# MCU.net
KiCad netlist of a schematic drawn in Altium Designer
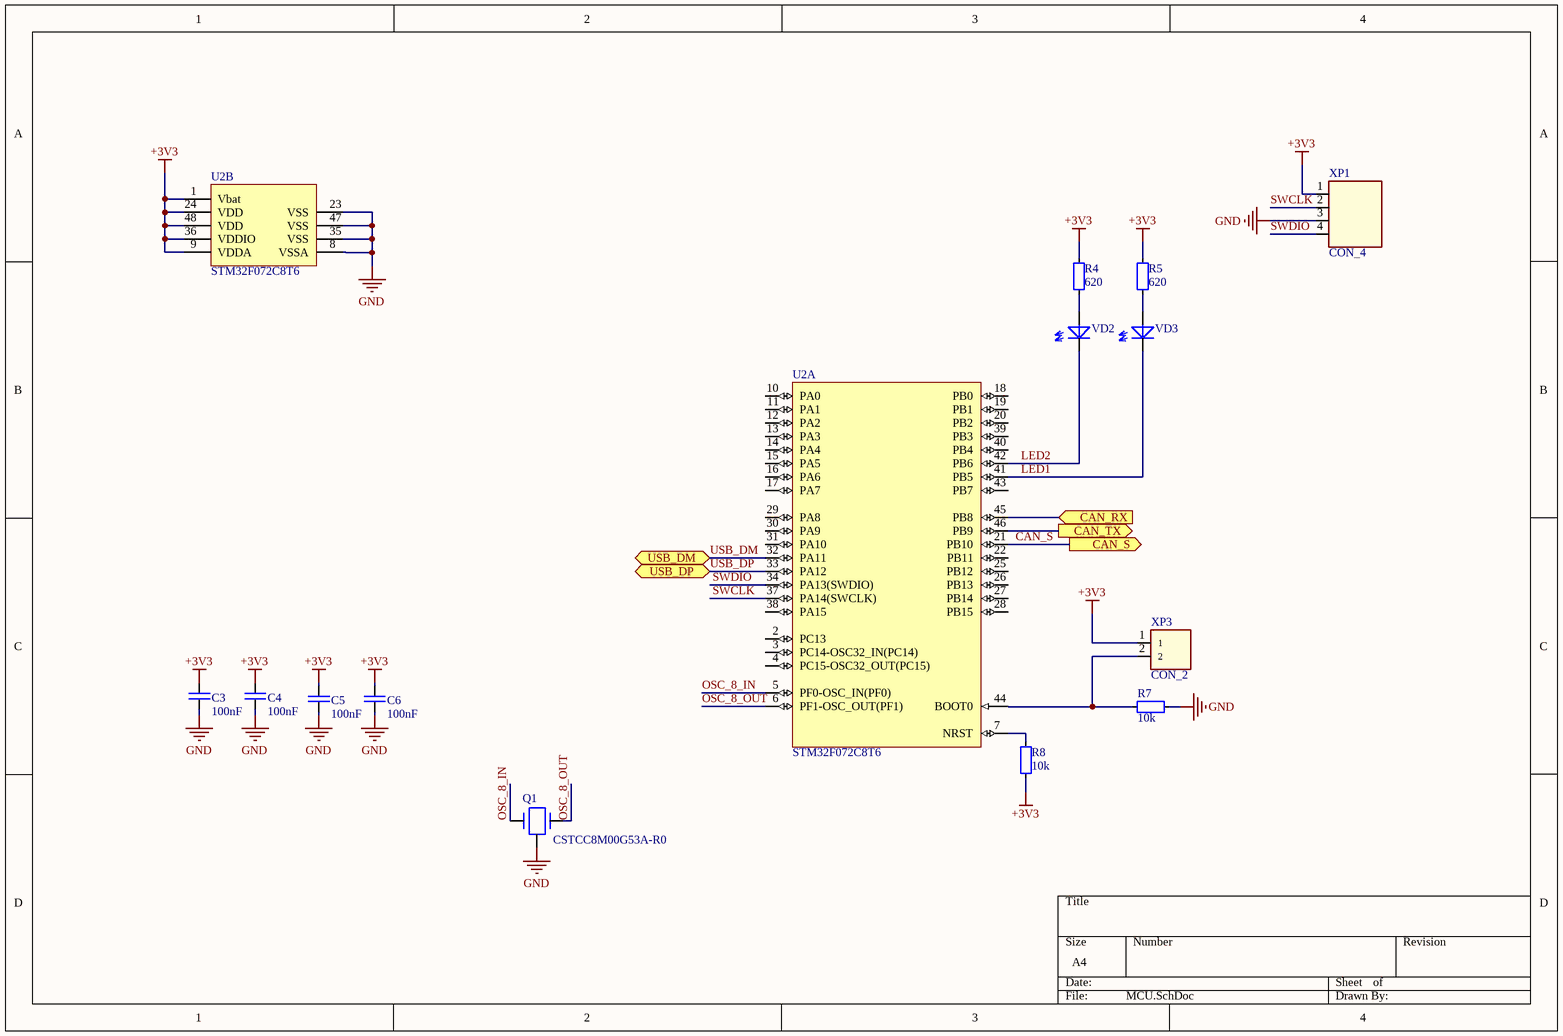
[diagram p0: MCU.SchDoc]

(export (version "E")
  (design (tool "Eeschema 10.0.6"))
  (components
    (comp (ref "C3")
      (value "100nF")
      (footprint "CAP_0603")
      (description "None polar capacitor")
      (libsource (lib "DISCRETE") (part "C_NONE_POLAR"))
    )
    (comp (ref "C4")
      (value "100nF")
      (footprint "CAP_0603")
      (description "None polar capacitor")
      (libsource (lib "DISCRETE") (part "C_NONE_POLAR"))
    )
    (comp (ref "C5")
      (value "100nF")
      (footprint "CAP_0603")
      (description "None polar capacitor")
      (libsource (lib "DISCRETE") (part "C_NONE_POLAR"))
    )
    (comp (ref "C6")
      (value "100nF")
      (footprint "CAP_0603")
      (description "None polar capacitor")
      (libsource (lib "DISCRETE") (part "C_NONE_POLAR"))
    )
    (comp (ref "Q1")
      (value "CSTCC8M00G53A-R0")
      (footprint "DISCRETE:CSTCC-CRYSTAL")
      (description "Crystal oscillator")
      (libsource (lib "DISCRETE") (part "CRYSTAL_CAP"))
    )
    (comp (ref "R4")
      (value "620")
      (footprint "DISCRETE:SMD_0603")
      (description "Resistor")
      (libsource (lib "") (part "RES_1"))
    )
    (comp (ref "R5")
      (value "620")
      (footprint "DISCRETE:SMD_0603")
      (description "Resistor")
      (libsource (lib "") (part "RES_1"))
    )
    (comp (ref "R7")
      (value "10k")
      (footprint "DISCRETE:SMD_0603")
      (description "Resistor")
      (libsource (lib "DISCRETE") (part "RES"))
    )
    (comp (ref "R8")
      (value "10k")
      (footprint "DISCRETE:SMD_0603")
      (description "Resistor")
      (libsource (lib "") (part "RES_1"))
    )
    (comp (ref "U2")
      (value "STM32F072C8T6")
      (footprint "ICs:QFN48-7x7-0.5")
      (fields (field (name "PARTNUMBER") "STM32F030C8T6"))
      (libsource (lib "ICs") (part "STM32F072C8T6"))
    )
    (comp (ref "VD2")
      (value "~")
      (footprint "DISCRETE:LED_0603")
      (description "LED")
      (libsource (lib "DISCRETE") (part "LED"))
    )
    (comp (ref "VD3")
      (value "~")
      (footprint "DISCRETE:LED_0603")
      (description "LED")
      (libsource (lib "DISCRETE") (part "LED"))
    )
    (comp (ref "XP1")
      (value "CON_4")
      (footprint "Connectors:HEAD_MICRO_SF_1.27-4")
      (libsource (lib "Connectors") (part "CON_4"))
    )
    (comp (ref "XP3")
      (value "CON_2")
      (footprint "Connectors:HEAD_MICRO_SF_1.27-2")
      (libsource (lib "Connectors") (part "CON_2"))
    )
  )
  (nets
    (net (code "1") (name "+3V3") (class "Default")
      (node (ref "C3") (pin "1") (pintype "passive"))
      (node (ref "C4") (pin "1") (pintype "passive"))
      (node (ref "C5") (pin "1") (pintype "passive"))
      (node (ref "C6") (pin "1") (pintype "passive"))
      (node (ref "R4") (pin "1") (pintype "passive"))
      (node (ref "R5") (pin "1") (pintype "passive"))
      (node (ref "R8") (pin "2") (pintype "passive"))
      (node (ref "U2") (pin "1") (pinfunction "Vbat_1") (pintype "power_in"))
      (node (ref "U2") (pin "24") (pinfunction "VDD_24") (pintype "power_in"))
      (node (ref "U2") (pin "36") (pinfunction "VDDIO_36") (pintype "power_in"))
      (node (ref "U2") (pin "48") (pinfunction "VDD_48") (pintype "power_in"))
      (node (ref "U2") (pin "9") (pinfunction "VDDA_9") (pintype "power_in"))
      (node (ref "XP1") (pin "1") (pinfunction "1_1") (pintype "passive"))
      (node (ref "XP3") (pin "1") (pinfunction "1_1") (pintype "passive"))
    )
    (net (code "2") (name "/CAN_RX") (class "Default")
      (node (ref "U2") (pin "45") (pinfunction "PB8_45") (pintype "bidirectional"))
    )
    (net (code "3") (name "/CAN_S") (class "Default")
      (node (ref "U2") (pin "21") (pinfunction "PB10_21") (pintype "bidirectional"))
    )
    (net (code "4") (name "/CAN_TX") (class "Default")
      (node (ref "U2") (pin "46") (pinfunction "PB9_46") (pintype "bidirectional"))
    )
    (net (code "5") (name "/LED1") (class "Default")
      (node (ref "U2") (pin "41") (pinfunction "PB5_41") (pintype "bidirectional"))
      (node (ref "VD3") (pin "1") (pinfunction "C_1") (pintype "passive"))
    )
    (net (code "6") (name "/LED2") (class "Default")
      (node (ref "U2") (pin "42") (pinfunction "PB6_42") (pintype "bidirectional"))
      (node (ref "VD2") (pin "1") (pinfunction "C_1") (pintype "passive"))
    )
    (net (code "7") (name "/OSC_8_IN") (class "Default")
      (node (ref "Q1") (pin "1") (pinfunction "1_1") (pintype "passive"))
      (node (ref "U2") (pin "5") (pinfunction "PF0-OSC_IN(PF0)_5") (pintype "bidirectional"))
    )
    (net (code "8") (name "/OSC_8_OUT") (class "Default")
      (node (ref "Q1") (pin "3") (pinfunction "3_3") (pintype "passive"))
      (node (ref "U2") (pin "6") (pinfunction "PF1-OSC_OUT(PF1)_6") (pintype "bidirectional"))
    )
    (net (code "9") (name "/SWCLK") (class "Default")
      (node (ref "U2") (pin "37") (pinfunction "PA14(SWCLK)_37") (pintype "bidirectional"))
      (node (ref "XP1") (pin "2") (pinfunction "2_2") (pintype "passive"))
    )
    (net (code "10") (name "/SWDIO") (class "Default")
      (node (ref "U2") (pin "34") (pinfunction "PA13(SWDIO)_34") (pintype "bidirectional"))
      (node (ref "XP1") (pin "4") (pinfunction "4_4") (pintype "passive"))
    )
    (net (code "11") (name "/USB_DM") (class "Default")
      (node (ref "U2") (pin "32") (pinfunction "PA11_32") (pintype "bidirectional"))
    )
    (net (code "12") (name "/USB_DP") (class "Default")
      (node (ref "U2") (pin "33") (pinfunction "PA12_33") (pintype "bidirectional"))
    )
    (net (code "13") (name "GND") (class "Default")
      (node (ref "C3") (pin "2") (pintype "passive"))
      (node (ref "C4") (pin "2") (pintype "passive"))
      (node (ref "C5") (pin "2") (pintype "passive"))
      (node (ref "C6") (pin "2") (pintype "passive"))
      (node (ref "Q1") (pin "2") (pinfunction "2_2") (pintype "passive"))
      (node (ref "R7") (pin "1") (pintype "passive"))
      (node (ref "U2") (pin "23") (pinfunction "VSS_23") (pintype "power_in"))
      (node (ref "U2") (pin "35") (pinfunction "VSS_35") (pintype "power_in"))
      (node (ref "U2") (pin "47") (pinfunction "VSS_47") (pintype "power_in"))
      (node (ref "U2") (pin "8") (pinfunction "VSSA_8") (pintype "power_in"))
      (node (ref "XP1") (pin "3") (pinfunction "3_3") (pintype "passive"))
    )
    (net (code "14") (name "Net-(U2A-BOOT0)") (class "Default")
      (node (ref "R7") (pin "2") (pintype "passive"))
      (node (ref "U2") (pin "44") (pinfunction "BOOT0_44") (pintype "input"))
      (node (ref "XP3") (pin "2") (pinfunction "2_2") (pintype "passive"))
    )
    (net (code "15") (name "Net-(U2A-NRST)") (class "Default")
      (node (ref "R8") (pin "1") (pintype "passive"))
      (node (ref "U2") (pin "7") (pinfunction "NRST_7") (pintype "bidirectional"))
    )
    (net (code "16") (name "Net-(VD2-A)") (class "Default")
      (node (ref "R4") (pin "2") (pintype "passive"))
      (node (ref "VD2") (pin "2") (pinfunction "A_2") (pintype "passive"))
    )
    (net (code "17") (name "Net-(VD3-A)") (class "Default")
      (node (ref "R5") (pin "2") (pintype "passive"))
      (node (ref "VD3") (pin "2") (pinfunction "A_2") (pintype "passive"))
    )
    (net (code "18") (name "unconnected-(U2A-PA0-Pad10)") (class "Default")
      (node (ref "U2") (pin "10") (pinfunction "PA0_10") (pintype "bidirectional"))
    )
    (net (code "19") (name "unconnected-(U2A-PA1-Pad11)") (class "Default")
      (node (ref "U2") (pin "11") (pinfunction "PA1_11") (pintype "bidirectional"))
    )
    (net (code "20") (name "unconnected-(U2A-PA2-Pad12)") (class "Default")
      (node (ref "U2") (pin "12") (pinfunction "PA2_12") (pintype "bidirectional"))
    )
    (net (code "21") (name "unconnected-(U2A-PA3-Pad13)") (class "Default")
      (node (ref "U2") (pin "13") (pinfunction "PA3_13") (pintype "bidirectional"))
    )
    (net (code "22") (name "unconnected-(U2A-PA4-Pad14)") (class "Default")
      (node (ref "U2") (pin "14") (pinfunction "PA4_14") (pintype "bidirectional"))
    )
    (net (code "23") (name "unconnected-(U2A-PA5-Pad15)") (class "Default")
      (node (ref "U2") (pin "15") (pinfunction "PA5_15") (pintype "bidirectional"))
    )
    (net (code "24") (name "unconnected-(U2A-PA6-Pad16)") (class "Default")
      (node (ref "U2") (pin "16") (pinfunction "PA6_16") (pintype "bidirectional"))
    )
    (net (code "25") (name "unconnected-(U2A-PA7-Pad17)") (class "Default")
      (node (ref "U2") (pin "17") (pinfunction "PA7_17") (pintype "bidirectional"))
    )
    (net (code "26") (name "unconnected-(U2A-PA8-Pad29)") (class "Default")
      (node (ref "U2") (pin "29") (pinfunction "PA8_29") (pintype "bidirectional"))
    )
    (net (code "27") (name "unconnected-(U2A-PA9-Pad30)") (class "Default")
      (node (ref "U2") (pin "30") (pinfunction "PA9_30") (pintype "bidirectional"))
    )
    (net (code "28") (name "unconnected-(U2A-PA10-Pad31)") (class "Default")
      (node (ref "U2") (pin "31") (pinfunction "PA10_31") (pintype "bidirectional"))
    )
    (net (code "29") (name "unconnected-(U2A-PA15-Pad38)") (class "Default")
      (node (ref "U2") (pin "38") (pinfunction "PA15_38") (pintype "bidirectional"))
    )
    (net (code "30") (name "unconnected-(U2A-PB0-Pad18)") (class "Default")
      (node (ref "U2") (pin "18") (pinfunction "PB0_18") (pintype "bidirectional"))
    )
    (net (code "31") (name "unconnected-(U2A-PB1-Pad19)") (class "Default")
      (node (ref "U2") (pin "19") (pinfunction "PB1_19") (pintype "bidirectional"))
    )
    (net (code "32") (name "unconnected-(U2A-PB2-Pad20)") (class "Default")
      (node (ref "U2") (pin "20") (pinfunction "PB2_20") (pintype "bidirectional"))
    )
    (net (code "33") (name "unconnected-(U2A-PB3-Pad39)") (class "Default")
      (node (ref "U2") (pin "39") (pinfunction "PB3_39") (pintype "bidirectional"))
    )
    (net (code "34") (name "unconnected-(U2A-PB4-Pad40)") (class "Default")
      (node (ref "U2") (pin "40") (pinfunction "PB4_40") (pintype "bidirectional"))
    )
    (net (code "35") (name "unconnected-(U2A-PB7-Pad43)") (class "Default")
      (node (ref "U2") (pin "43") (pinfunction "PB7_43") (pintype "bidirectional"))
    )
    (net (code "36") (name "unconnected-(U2A-PB11-Pad22)") (class "Default")
      (node (ref "U2") (pin "22") (pinfunction "PB11_22") (pintype "bidirectional"))
    )
    (net (code "37") (name "unconnected-(U2A-PB12-Pad25)") (class "Default")
      (node (ref "U2") (pin "25") (pinfunction "PB12_25") (pintype "bidirectional"))
    )
    (net (code "38") (name "unconnected-(U2A-PB13-Pad26)") (class "Default")
      (node (ref "U2") (pin "26") (pinfunction "PB13_26") (pintype "bidirectional"))
    )
    (net (code "39") (name "unconnected-(U2A-PB14-Pad27)") (class "Default")
      (node (ref "U2") (pin "27") (pinfunction "PB14_27") (pintype "bidirectional"))
    )
    (net (code "40") (name "unconnected-(U2A-PB15-Pad28)") (class "Default")
      (node (ref "U2") (pin "28") (pinfunction "PB15_28") (pintype "bidirectional"))
    )
    (net (code "41") (name "unconnected-(U2A-PC13-Pad2)") (class "Default")
      (node (ref "U2") (pin "2") (pinfunction "PC13_2") (pintype "bidirectional"))
    )
    (net (code "42") (name "unconnected-(U2A-PC14-OSC32_IN(PC14)-Pad3)") (class "Default")
      (node (ref "U2") (pin "3") (pinfunction "PC14-OSC32_IN(PC14)_3") (pintype "bidirectional"))
    )
    (net (code "43") (name "unconnected-(U2A-PC15-OSC32_OUT(PC15)-Pad4)") (class "Default")
      (node (ref "U2") (pin "4") (pinfunction "PC15-OSC32_OUT(PC15)_4") (pintype "bidirectional"))
    )
  )
)
